# POWER.net
KiCad netlist of a schematic drawn in Altium Designer
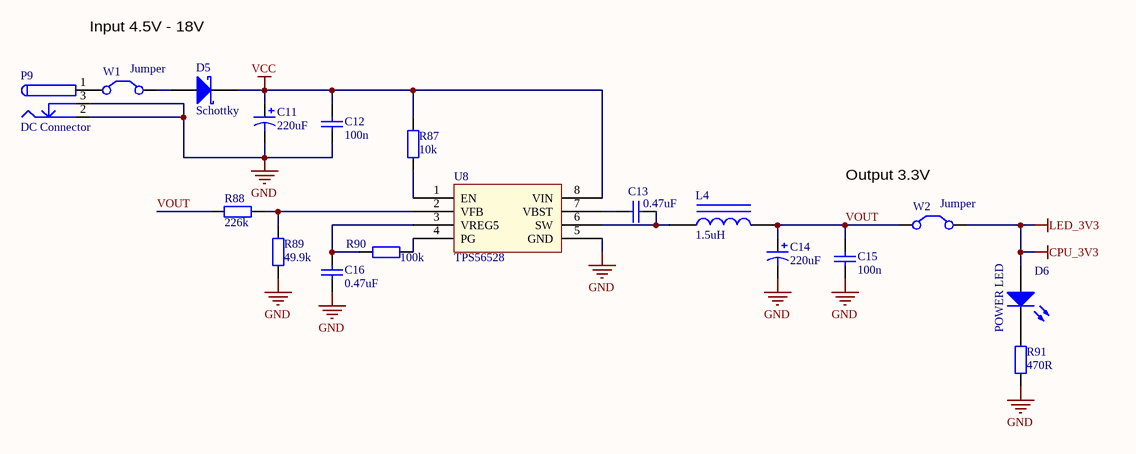
[diagram p0: POWER.SchDoc]

(export (version "E")
  (design (tool "Eeschema 10.0.6"))
  (components
    (comp (ref "C11")
      (value "220uF")
      (footprint "SMD CAPACITOR 220uF")
      (description "Capacitor")
      (fields (field (name "PUBLISHER") "Altium Limited"))
      (libsource (lib "Miscellaneous Devices") (part "Cap Pol1"))
    )
    (comp (ref "C12")
      (value "100n")
      (footprint "1608[0603]")
      (description "Capacitor")
      (fields (field (name "PUBLISHER") "Altium Limited"))
      (libsource (lib "Miscellaneous Devices") (part "Cap"))
    )
    (comp (ref "C13")
      (value "0.47uF")
      (footprint "1608[0603]")
      (description "Capacitor")
      (fields (field (name "PUBLISHER") "Altium Limited"))
      (libsource (lib "Miscellaneous Devices") (part "Cap"))
    )
    (comp (ref "C14")
      (value "220uF")
      (footprint "SMD CAPACITOR 220uF")
      (description "Capacitor")
      (fields (field (name "PUBLISHER") "Altium Limited"))
      (libsource (lib "Miscellaneous Devices") (part "Cap Pol1"))
    )
    (comp (ref "C15")
      (value "100n")
      (footprint "1608[0603]")
      (description "Capacitor")
      (fields (field (name "PUBLISHER") "Altium Limited"))
      (libsource (lib "Miscellaneous Devices") (part "Cap"))
    )
    (comp (ref "C16")
      (value "0.47uF")
      (footprint "1608[0603]")
      (description "Capacitor")
      (fields (field (name "PUBLISHER") "Altium Limited"))
      (libsource (lib "Miscellaneous Devices") (part "Cap"))
    )
    (comp (ref "D5")
      (value "Schottky")
      (footprint "SMB")
      (description "Schottky Diode")
      (fields (field (name "PUBLISHER") "Altium Limited"))
      (libsource (lib "Miscellaneous Devices") (part "D Schottky"))
    )
    (comp (ref "D6")
      (value "POWER LED")
      (footprint "LED-1")
      (description "Typical INFRARED GaAs LED")
      (fields (field (name "PUBLISHER") "Altium Limited"))
      (libsource (lib "Miscellaneous Devices") (part "LED0"))
    )
    (comp (ref "L4")
      (value "1.5uH")
      (footprint "Inductor")
      (description "Magnetic-Core Inductor")
      (fields (field (name "PUBLISHER") "Altium Limited"))
      (libsource (lib "Miscellaneous Devices") (part "Inductor Iron"))
    )
    (comp (ref "P9")
      (value "DC Connector")
      (footprint "DC Connector")
      (description "DC Power Connector")
      (libsource (lib "LukaLIBRARY") (part "DC Connector"))
    )
    (comp (ref "R87")
      (value "10k")
      (footprint "1608[0603]")
      (description "Resistor")
      (fields (field (name "PUBLISHER") "Altium Limited"))
      (libsource (lib "Miscellaneous Devices") (part "Res2"))
    )
    (comp (ref "R88")
      (value "226k")
      (footprint "1608[0603]")
      (description "Resistor")
      (fields (field (name "PUBLISHER") "Altium Limited"))
      (libsource (lib "") (part "Res2_1"))
    )
    (comp (ref "R89")
      (value "49.9k")
      (footprint "1608[0603]")
      (description "Resistor")
      (fields (field (name "PUBLISHER") "Altium Limited"))
      (libsource (lib "Miscellaneous Devices") (part "Res2"))
    )
    (comp (ref "R90")
      (value "100k")
      (footprint "1608[0603]")
      (description "Resistor")
      (fields (field (name "PUBLISHER") "Altium Limited"))
      (libsource (lib "") (part "Res2_1"))
    )
    (comp (ref "R91")
      (value "470R")
      (footprint "1608[0603]")
      (description "Resistor")
      (fields (field (name "PUBLISHER") "Altium Limited"))
      (libsource (lib "Miscellaneous Devices") (part "Res2"))
    )
    (comp (ref "U8")
      (value "TPS56528")
      (footprint "TPS56528")
      (description "Step-Down Converter 5A 4.5V-18V")
      (libsource (lib "LP_Lib") (part "TPS56528"))
    )
    (comp (ref "W1")
      (value "Jumper")
      (footprint "HDR1X2")
      (description "Jumper Wire")
      (fields (field (name "PUBLISHER") "Altium Limited"))
      (libsource (lib "Miscellaneous Devices") (part "Jumper"))
    )
    (comp (ref "W2")
      (value "Jumper")
      (footprint "HDR1X2")
      (description "Jumper Wire")
      (fields (field (name "PUBLISHER") "Altium Limited"))
      (libsource (lib "Miscellaneous Devices") (part "Jumper"))
    )
  )
  (nets
    (net (code "1") (name "/VOUT") (class "Default")
      (node (ref "C14") (pin "1") (pinfunction "1_1") (pintype "passive"))
      (node (ref "C15") (pin "1") (pinfunction "1_1") (pintype "passive"))
      (node (ref "L4") (pin "2") (pinfunction "2_2") (pintype "passive"))
      (node (ref "R88") (pin "2") (pinfunction "2_2") (pintype "passive"))
      (node (ref "W2") (pin "1") (pinfunction "C1_1") (pintype "passive"))
    )
    (net (code "2") (name "CPU_3V3") (class "Default")
      (node (ref "D6") (pin "1") (pinfunction "A_1") (pintype "passive"))
      (node (ref "W2") (pin "2") (pinfunction "C2_2") (pintype "passive"))
    )
    (net (code "3") (name "GND") (class "Default")
      (node (ref "C11") (pin "2") (pinfunction "2_2") (pintype "passive"))
      (node (ref "C12") (pin "2") (pinfunction "2_2") (pintype "passive"))
      (node (ref "C14") (pin "2") (pinfunction "2_2") (pintype "passive"))
      (node (ref "C15") (pin "2") (pinfunction "2_2") (pintype "passive"))
      (node (ref "C16") (pin "2") (pinfunction "2_2") (pintype "passive"))
      (node (ref "P9") (pin "2") (pinfunction "2_2") (pintype "power_in"))
      (node (ref "P9") (pin "3") (pinfunction "3_3") (pintype "power_in"))
      (node (ref "R89") (pin "1") (pinfunction "1_1") (pintype "passive"))
      (node (ref "R91") (pin "1") (pinfunction "1_1") (pintype "passive"))
      (node (ref "U8") (pin "5") (pinfunction "GND_5") (pintype "passive"))
    )
    (net (code "4") (name "Net-(D5-A)") (class "Default")
      (node (ref "D5") (pin "1") (pinfunction "A_1") (pintype "passive"))
      (node (ref "W1") (pin "2") (pinfunction "C2_2") (pintype "passive"))
    )
    (net (code "5") (name "Net-(D6-K)") (class "Default")
      (node (ref "D6") (pin "2") (pinfunction "K_2") (pintype "passive"))
      (node (ref "R91") (pin "2") (pinfunction "2_2") (pintype "passive"))
    )
    (net (code "6") (name "Net-(U8-EN)") (class "Default")
      (node (ref "R87") (pin "1") (pinfunction "1_1") (pintype "passive"))
      (node (ref "U8") (pin "1") (pinfunction "EN_1") (pintype "passive"))
    )
    (net (code "7") (name "Net-(U8-PG)") (class "Default")
      (node (ref "R90") (pin "1") (pinfunction "1_1") (pintype "passive"))
      (node (ref "U8") (pin "4") (pinfunction "PG_4") (pintype "passive"))
    )
    (net (code "8") (name "Net-(U8-SW)") (class "Default")
      (node (ref "C13") (pin "2") (pinfunction "2_2") (pintype "passive"))
      (node (ref "L4") (pin "1") (pinfunction "1_1") (pintype "passive"))
      (node (ref "U8") (pin "6") (pinfunction "SW_6") (pintype "passive"))
    )
    (net (code "9") (name "Net-(U8-VBST)") (class "Default")
      (node (ref "C13") (pin "1") (pinfunction "1_1") (pintype "passive"))
      (node (ref "U8") (pin "7") (pinfunction "VBST_7") (pintype "passive"))
    )
    (net (code "10") (name "Net-(U8-VFB)") (class "Default")
      (node (ref "R88") (pin "1") (pinfunction "1_1") (pintype "passive"))
      (node (ref "R89") (pin "2") (pinfunction "2_2") (pintype "passive"))
      (node (ref "U8") (pin "2") (pinfunction "VFB_2") (pintype "passive"))
    )
    (net (code "11") (name "Net-(U8-VREG5)") (class "Default")
      (node (ref "C16") (pin "1") (pinfunction "1_1") (pintype "passive"))
      (node (ref "R90") (pin "2") (pinfunction "2_2") (pintype "passive"))
      (node (ref "U8") (pin "3") (pinfunction "VREG5_3") (pintype "passive"))
    )
    (net (code "12") (name "Net-(W1-C1)") (class "Default")
      (node (ref "P9") (pin "1") (pinfunction "1_1") (pintype "power_in"))
      (node (ref "W1") (pin "1") (pinfunction "C1_1") (pintype "passive"))
    )
    (net (code "13") (name "VCC") (class "Default")
      (node (ref "C11") (pin "1") (pinfunction "1_1") (pintype "passive"))
      (node (ref "C12") (pin "1") (pinfunction "1_1") (pintype "passive"))
      (node (ref "D5") (pin "2") (pinfunction "K_2") (pintype "passive"))
      (node (ref "R87") (pin "2") (pinfunction "2_2") (pintype "passive"))
      (node (ref "U8") (pin "8") (pinfunction "VIN_8") (pintype "passive"))
    )
  )
)
